# schematic-copy_2026-08-19.net
KiCad netlist of a schematic drawn in Altium Designer
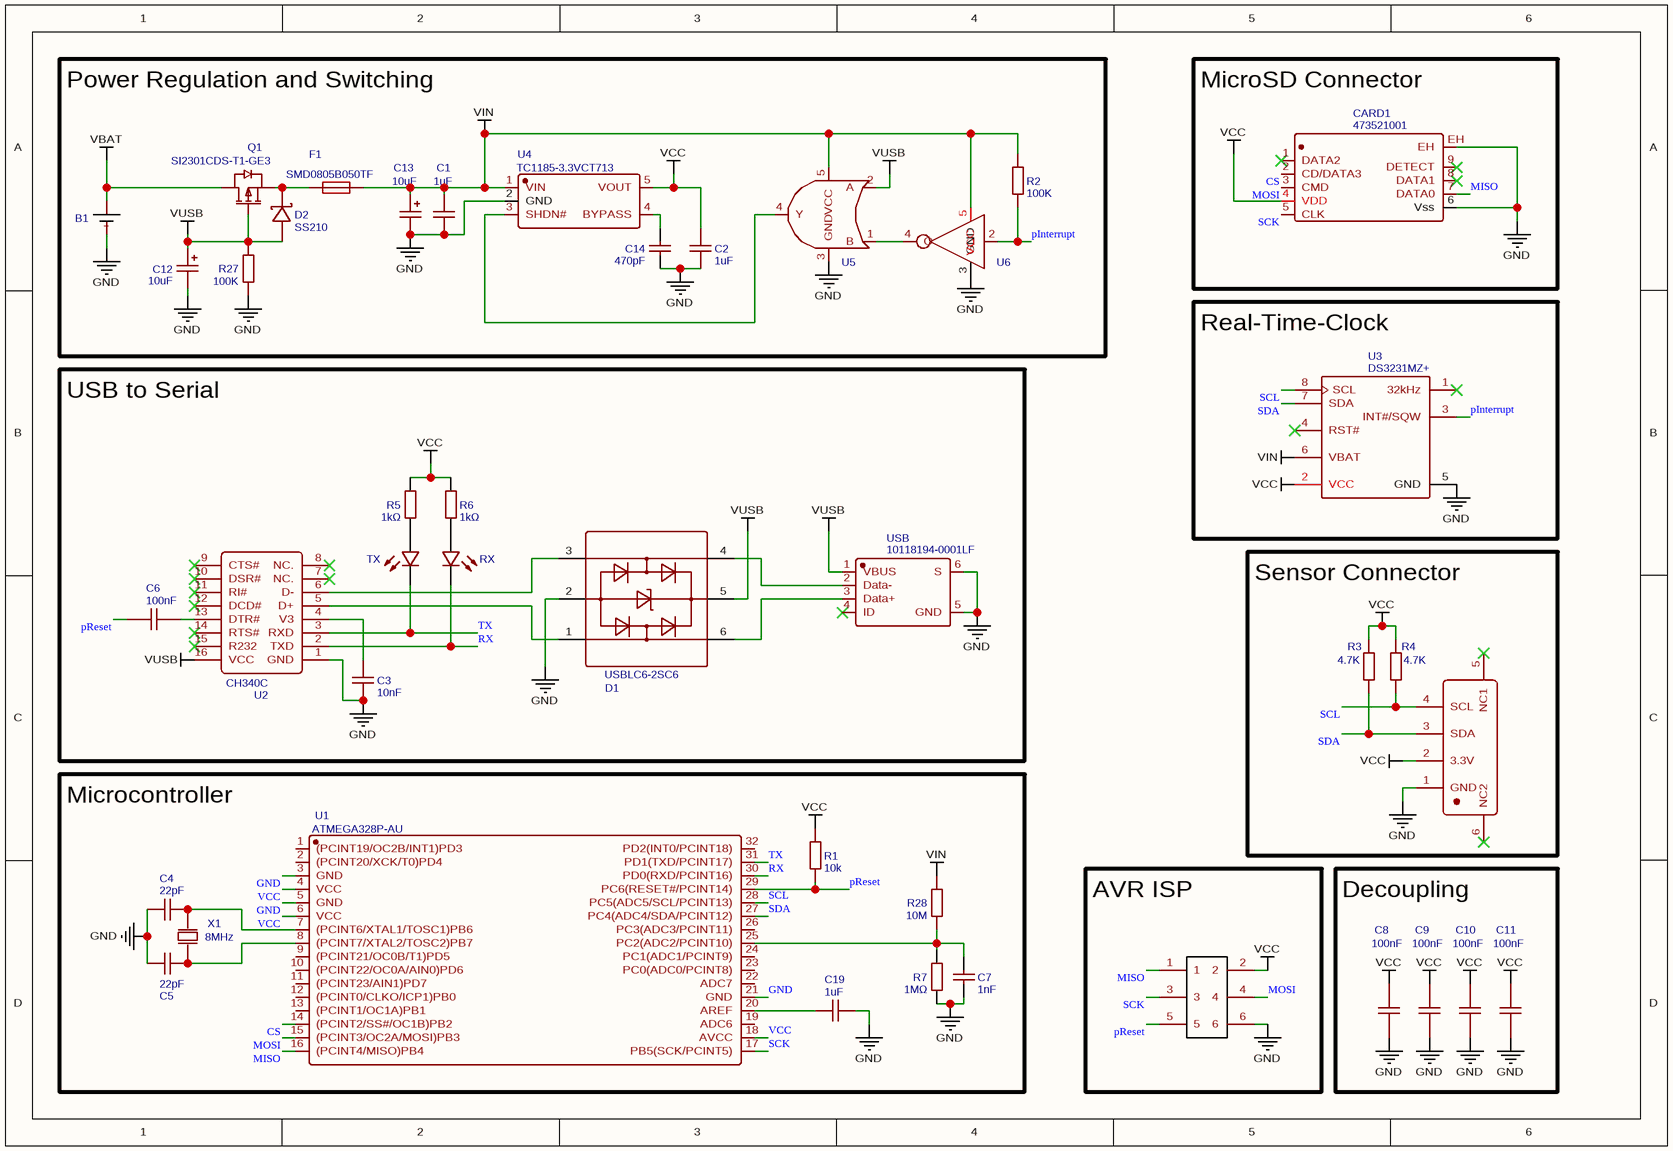
[diagram p0: schematic-copy_2026-08-19.schdoc]

(export (version "E")
  (design (tool "Eeschema 10.0.6"))
  (components
    (comp (ref "B1")
      (value "KEYSTONE 2460 1XAA")
      (fields
        (field (name "MANUFACTURER") "Keystone Electronics")
        (field (name "MANUFACTURER PART") "2460")
        (field (name "CONTRIBUTOR") "montezuma1970")
      )
      (libsource (lib "altium-import") (part "root_0_KEYSTONE 2460 1XAA_"))
    )
    (comp (ref "C1")
      (value "1uF")
      (fields (field (name "MANUFACTURER PART") "CL10A105KB8NNNC") (field (name "MANUFACTURER") "SAMSUNG"))
      (libsource (lib "altium-import") (part "root_1_1uF_"))
    )
    (comp (ref "C2")
      (value "1uF")
      (fields (field (name "MANUFACTURER PART") "CL10A105KB8NNNC") (field (name "MANUFACTURER") "SAMSUNG"))
      (libsource (lib "altium-import") (part "root_3_1uF_"))
    )
    (comp (ref "C3")
      (value "10nF")
      (fields (field (name "MANUFACTURER") "FH(风华)") (field (name "MANUFACTURER PART") "0603B103K500NT"))
      (libsource (lib "altium-import") (part "root_3_10nF_"))
    )
    (comp (ref "C4")
      (value "22pF")
      (fields (field (name "MANUFACTURER PART") "CL10C220JB8NNNC") (field (name "MANUFACTURER") "SAMSUNG"))
      (libsource (lib "altium-import") (part "root_2_22pF_"))
    )
    (comp (ref "C5")
      (value "22pF")
      (fields (field (name "MANUFACTURER PART") "CL10C220JB8NNNC") (field (name "MANUFACTURER") "SAMSUNG"))
      (libsource (lib "altium-import") (part "root_0_22pF_"))
    )
    (comp (ref "C6")
      (value "100nF")
      (fields (field (name "MANUFACTURER") "YAGEO") (field (name "MANUFACTURER PART") "CC0603KRX7R9BB104"))
      (libsource (lib "altium-import") (part "root_2_100nF_"))
    )
    (comp (ref "C7")
      (value "1nF")
      (fields
        (field (name "MANUFACTURER PART") "CL10B102KB8NNNC")
        (field (name "MANUFACTURER") "SAMSUNG(三星)")
      )
      (libsource (lib "altium-import") (part "root_1_1nF_"))
    )
    (comp (ref "C8")
      (value "100nF")
      (fields (field (name "MANUFACTURER") "YAGEO") (field (name "MANUFACTURER PART") "CC0603KRX7R9BB104"))
      (libsource (lib "altium-import") (part "root_1_100nF_"))
    )
    (comp (ref "C9")
      (value "100nF")
      (fields (field (name "MANUFACTURER") "YAGEO") (field (name "MANUFACTURER PART") "CC0603KRX7R9BB104"))
      (libsource (lib "altium-import") (part "root_1_100nF_"))
    )
    (comp (ref "C10")
      (value "100nF")
      (fields (field (name "MANUFACTURER") "YAGEO") (field (name "MANUFACTURER PART") "CC0603KRX7R9BB104"))
      (libsource (lib "altium-import") (part "root_1_100nF_"))
    )
    (comp (ref "C11")
      (value "100nF")
      (fields (field (name "MANUFACTURER") "YAGEO") (field (name "MANUFACTURER PART") "CC0603KRX7R9BB104"))
      (libsource (lib "altium-import") (part "root_1_100nF_"))
    )
    (comp (ref "C12")
      (value "10uF")
      (fields (field (name "MANUFACTURER") "AVX") (field (name "MANUFACTURER PART") "TAJA106K016RNJ"))
      (libsource (lib "altium-import") (part "root_1_10uF_"))
    )
    (comp (ref "C13")
      (value "10uF")
      (fields (field (name "MANUFACTURER") "AVX") (field (name "MANUFACTURER PART") "TAJA106K016RNJ"))
      (libsource (lib "altium-import") (part "root_1_10uF_"))
    )
    (comp (ref "C14")
      (value "470pF")
      (fields (field (name "MANUFACTURER") "FH(风华)") (field (name "MANUFACTURER PART") "0603B471K500NT"))
      (libsource (lib "altium-import") (part "root_1_470pF_"))
    )
    (comp (ref "C19")
      (value "1uF")
      (fields (field (name "MANUFACTURER PART") "CL10A105KB8NNNC") (field (name "MANUFACTURER") "SAMSUNG"))
      (libsource (lib "altium-import") (part "root_2_1uF_"))
    )
    (comp (ref "CARD1")
      (value "473521001")
      (fields (field (name "MANUFACTURER") "MOLEX") (field (name "CONTRIBUTOR") "LCSC"))
      (libsource (lib "altium-import") (part "root_0_473521001_"))
    )
    (comp (ref "D1")
      (value "USBLC6-2SC6")
      (fields (field (name "MANUFACTURER") "ST(意法半导体)"))
      (libsource (lib "altium-import") (part "root_0_USBLC6-2SC6_"))
    )
    (comp (ref "D2")
      (value "SS210")
      (fields (field (name "MANUFACTURER") "MDD"))
      (libsource (lib "altium-import") (part "root_3_SS210_"))
    )
    (comp (ref "F1")
      (value "SMD0805B050TF")
      (fields (field (name "MANUFACTURER") "Brightking(君耀电子)") (field (name "CONTRIBUTOR") "LCSC"))
      (libsource (lib "altium-import") (part "root_0_SMD0805B050TF_"))
    )
    (comp (ref "ICSP")
      (value "ICSP_2X3")
      (fields (field (name "CONTRIBUTOR") "hvergelmir.eed04"))
      (libsource (lib "altium-import") (part "root_0_ICSP_2X3_"))
    )
    (comp (ref "Q1")
      (value "SI2301CDS-T1-GE3")
      (fields (field (name "MANUFACTURER") "VISHAY"))
      (libsource (lib "altium-import") (part "root_3_SI2301CDS-T1-GE3_"))
    )
    (comp (ref "R1")
      (value "10k")
      (fields (field (name "MANUFACTURER") "UniOhm") (field (name "MANUFACTURER PART") "0603WAF1002T5E"))
      (libsource (lib "altium-import") (part "root_1_10k_"))
    )
    (comp (ref "R2")
      (value "100K")
      (fields (field (name "MANUFACTURER") "UniOhm") (field (name "MANUFACTURER PART") "0603WAF1003T5E"))
      (libsource (lib "altium-import") (part "root_1_100K_"))
    )
    (comp (ref "R3")
      (value "4.7K")
      (fields (field (name "MANUFACTURER") "UniOhm") (field (name "MANUFACTURER PART") "0603WAF4701T5E"))
      (libsource (lib "altium-import") (part "root_1_4.7K_"))
    )
    (comp (ref "R4")
      (value "4.7K")
      (fields (field (name "MANUFACTURER") "UniOhm") (field (name "MANUFACTURER PART") "0603WAF4701T5E"))
      (libsource (lib "altium-import") (part "root_1_4.7K_"))
    )
    (comp (ref "R5")
      (value "1kΩ")
      (fields
        (field (name "MANUFACTURER") "UNI-ROYAL(厚声)")
        (field (name "MANUFACTURER PART") "0603WAF1001T5E")
      )
      (libsource (lib "altium-import") (part "root_1_1kΩ_"))
    )
    (comp (ref "R6")
      (value "1kΩ")
      (fields
        (field (name "MANUFACTURER") "UNI-ROYAL(厚声)")
        (field (name "MANUFACTURER PART") "0603WAF1001T5E")
      )
      (libsource (lib "altium-import") (part "root_1_1kΩ_"))
    )
    (comp (ref "R7")
      (value "1MΩ")
      (fields
        (field (name "MANUFACTURER") "UNI-ROYAL(厚声)")
        (field (name "MANUFACTURER PART") "0603WAF1004T5E")
      )
      (libsource (lib "altium-import") (part "root_1_1MΩ_"))
    )
    (comp (ref "R27")
      (value "100K")
      (fields (field (name "MANUFACTURER") "UniOhm") (field (name "MANUFACTURER PART") "0603WAF1003T5E"))
      (libsource (lib "altium-import") (part "root_1_100K_"))
    )
    (comp (ref "R28")
      (value "10M")
      (fields (field (name "MANUFACTURER") "UniOhm") (field (name "MANUFACTURER PART") "0603WAF1005T5E"))
      (libsource (lib "altium-import") (part "root_1_10M_"))
    )
    (comp (ref "RX")
      (value "19-213/Y2C-CQ2R2L/3T(CY)")
      (fields (field (name "MANUFACTURER") "EVERLIGHT(亿光)"))
      (libsource (lib "altium-import") (part "root_3_19-213/Y2C-CQ2R2L/3T(CY)_"))
    )
    (comp (ref "TX")
      (value "19-213/Y2C-CQ2R2L/3T(CY)")
      (fields (field (name "MANUFACTURER") "EVERLIGHT(亿光)"))
      (libsource (lib "") (part "root_3_19-213/Y2C-CQ2R2L/3T(CY)__1"))
    )
    (comp (ref "U1")
      (value "ATMEGA328P-AU")
      (fields (field (name "MANUFACTURER") "MICROCHIP"))
      (libsource (lib "altium-import") (part "root_0_ATMEGA328P-AU_"))
    )
    (comp (ref "U2")
      (value "CH340C")
      (fields (field (name "MANUFACTURER") "WCH"))
      (libsource (lib "altium-import") (part "root_0_CH340C_"))
    )
    (comp (ref "U3")
      (value "DS3231MZ+")
      (fields (field (name "MANUFACTURER") "MAXIM(美信)") (field (name "MANUFACTURER PART") "DS3231MZ+TRL"))
      (libsource (lib "altium-import") (part "root_0_DS3231MZ+_"))
    )
    (comp (ref "U4")
      (value "TC1185-3.3VCT713")
      (fields (field (name "MANUFACTURER") "MICROCHIP(美国微芯)"))
      (libsource (lib "altium-import") (part "root_0_TC1185-3.3VCT713_"))
    )
    (comp (ref "U5")
      (value "74AHC1G32GW,125")
      (fields (field (name "MANUFACTURER") "Nexperia") (field (name "CONTRIBUTOR") "Ted Langhorst"))
      (libsource (lib "altium-import") (part "root_0_74AHC1G32GW,125_"))
    )
    (comp (ref "U6")
      (value "SN74LVC1G14DCKR")
      (fields (field (name "MANUFACTURER") "TI(德州仪器)"))
      (libsource (lib "altium-import") (part "root_2_SN74LVC1G14DCKR_"))
    )
    (comp (ref "U11")
      (value "QWIIC")
      (fields (field (name "MANUFACTURER") "JST Sales America") (field (name "CONTRIBUTOR") "donhagen"))
      (libsource (lib "altium-import") (part "root_1_QWIIC_"))
    )
    (comp (ref "USB")
      (value "10118194-0001LF")
      (fields (field (name "MANUFACTURER") "Amphenol ICC") (field (name "CONTRIBUTOR") "LCSC"))
      (libsource (lib "altium-import") (part "root_0_10118194-0001LF_"))
    )
    (comp (ref "X1")
      (value "8MHz")
      (fields (field (name "MANUFACTURER") "YXC") (field (name "MANUFACTURER PART") "X50328MSB2GI"))
      (libsource (lib "altium-import") (part "root_1_8MHz_"))
    )
  )
  (nets
    (net (code "1") (name "/CS") (class "Default")
      (node (ref "CARD1") (pin "2") (pinfunction "CD/DATA3_2") (pintype "passive"))
      (node (ref "U1") (pin "14") (pinfunction "(PCINT2/SS#/OC1B)PB2_14") (pintype "passive"))
    )
    (net (code "2") (name "/MISO") (class "Default")
      (node (ref "CARD1") (pin "7") (pinfunction "DATA0_7") (pintype "passive"))
      (node (ref "ICSP") (pin "1") (pinfunction "1_1") (pintype "passive"))
      (node (ref "U1") (pin "16") (pinfunction "(PCINT4/MISO)PB4_16") (pintype "passive"))
    )
    (net (code "3") (name "/MOSI") (class "Default")
      (node (ref "CARD1") (pin "3") (pinfunction "CMD_3") (pintype "passive"))
      (node (ref "ICSP") (pin "4") (pinfunction "4_4") (pintype "passive"))
      (node (ref "U1") (pin "15") (pinfunction "(PCINT3/OC2A/MOSI)PB3_15") (pintype "passive"))
    )
    (net (code "4") (name "/RX") (class "Default")
      (node (ref "RX") (pin "2") (pinfunction "C_2") (pintype "passive"))
      (node (ref "U1") (pin "30") (pinfunction "PD0(RXD/PCINT16)_30") (pintype "passive"))
      (node (ref "U2") (pin "2") (pinfunction "TXD_2") (pintype "passive"))
    )
    (net (code "5") (name "/SCK") (class "Default")
      (node (ref "CARD1") (pin "5") (pinfunction "CLK_5") (pintype "passive"))
      (node (ref "ICSP") (pin "3") (pinfunction "3_3") (pintype "passive"))
      (node (ref "U1") (pin "17") (pinfunction "PB5(SCK/PCINT5)_17") (pintype "passive"))
    )
    (net (code "6") (name "/SCL") (class "Default")
      (node (ref "R4") (pin "1") (pinfunction "1_1") (pintype "passive"))
      (node (ref "U1") (pin "28") (pinfunction "PC5(ADC5/SCL/PCINT13)_28") (pintype "passive"))
      (node (ref "U11") (pin "4") (pinfunction "SCL_4") (pintype "passive"))
      (node (ref "U3") (pin "8") (pinfunction "SCL_8") (pintype "passive"))
    )
    (net (code "7") (name "/SDA") (class "Default")
      (node (ref "R3") (pin "1") (pinfunction "1_1") (pintype "passive"))
      (node (ref "U1") (pin "27") (pinfunction "PC4(ADC4/SDA/PCINT12)_27") (pintype "passive"))
      (node (ref "U11") (pin "3") (pinfunction "SDA_3") (pintype "passive"))
      (node (ref "U3") (pin "7") (pinfunction "SDA_7") (pintype "passive"))
    )
    (net (code "8") (name "/TX") (class "Default")
      (node (ref "TX") (pin "2") (pinfunction "C_2") (pintype "passive"))
      (node (ref "U1") (pin "31") (pinfunction "PD1(TXD/PCINT17)_31") (pintype "passive"))
      (node (ref "U2") (pin "3") (pinfunction "RXD_3") (pintype "passive"))
    )
    (net (code "9") (name "/pInterrupt") (class "Default")
      (node (ref "R2") (pin "1") (pinfunction "1_1") (pintype "passive"))
      (node (ref "U3") (pin "3") (pinfunction "INT#/SQW_3") (pintype "passive"))
      (node (ref "U6") (pin "2") (pinfunction "I_2") (pintype "passive"))
    )
    (net (code "10") (name "/pReset") (class "Default")
      (node (ref "C6") (pin "2") (pinfunction "2_2") (pintype "passive"))
      (node (ref "ICSP") (pin "5") (pinfunction "5_5") (pintype "passive"))
      (node (ref "R1") (pin "1") (pinfunction "1_1") (pintype "passive"))
      (node (ref "U1") (pin "29") (pinfunction "PC6(RESET#/PCINT14)_29") (pintype "passive"))
    )
    (net (code "11") (name "GND") (class "Default")
      (node (ref "B1") (pin "2") (pinfunction "-_2") (pintype "passive"))
      (node (ref "C1") (pin "1") (pinfunction "1_1") (pintype "passive"))
      (node (ref "C10") (pin "1") (pinfunction "1_1") (pintype "passive"))
      (node (ref "C11") (pin "1") (pinfunction "1_1") (pintype "passive"))
      (node (ref "C12") (pin "2") (pinfunction "2_2") (pintype "passive"))
      (node (ref "C13") (pin "2") (pinfunction "2_2") (pintype "passive"))
      (node (ref "C14") (pin "1") (pinfunction "1_1") (pintype "passive"))
      (node (ref "C19") (pin "1") (pinfunction "1_1") (pintype "passive"))
      (node (ref "C2") (pin "2") (pinfunction "2_2") (pintype "passive"))
      (node (ref "C3") (pin "2") (pinfunction "2_2") (pintype "passive"))
      (node (ref "C4") (pin "2") (pinfunction "2_2") (pintype "passive"))
      (node (ref "C5") (pin "1") (pinfunction "1_1") (pintype "passive"))
      (node (ref "C7") (pin "1") (pinfunction "1_1") (pintype "passive"))
      (node (ref "C8") (pin "1") (pinfunction "1_1") (pintype "passive"))
      (node (ref "C9") (pin "1") (pinfunction "1_1") (pintype "passive"))
      (node (ref "CARD1") (pin "6") (pinfunction "Vss_6") (pintype "passive"))
      (node (ref "CARD1") (pin "EH") (pinfunction "EH_EH") (pintype "passive"))
      (node (ref "D1") (pin "2") (pinfunction "2_2") (pintype "passive"))
      (node (ref "ICSP") (pin "6") (pinfunction "6_6") (pintype "passive"))
      (node (ref "R27") (pin "1") (pinfunction "1_1") (pintype "passive"))
      (node (ref "R7") (pin "1") (pinfunction "1_1") (pintype "passive"))
      (node (ref "U1") (pin "21") (pinfunction "GND_21") (pintype "passive"))
      (node (ref "U1") (pin "3") (pinfunction "GND_3") (pintype "passive"))
      (node (ref "U1") (pin "5") (pinfunction "GND_5") (pintype "passive"))
      (node (ref "U11") (pin "1") (pinfunction "GND_1") (pintype "passive"))
      (node (ref "U2") (pin "1") (pinfunction "GND_1") (pintype "passive"))
      (node (ref "U3") (pin "5") (pinfunction "GND_5") (pintype "passive"))
      (node (ref "U4") (pin "2") (pinfunction "GND_2") (pintype "passive"))
      (node (ref "U5") (pin "3") (pinfunction "GND_3") (pintype "passive"))
      (node (ref "U6") (pin "3") (pinfunction "GND_3") (pintype "passive"))
      (node (ref "USB") (pin "5") (pinfunction "GND_5") (pintype "passive"))
      (node (ref "USB") (pin "6") (pinfunction "S_6") (pintype "passive"))
    )
    (net (code "12") (name "Net-(D2-K)") (class "Default")
      (node (ref "D2") (pin "1") (pinfunction "K_1") (pintype "passive"))
      (node (ref "F1") (pin "1") (pinfunction "1_1") (pintype "passive"))
      (node (ref "Q1") (pin "2") (pinfunction "S_2") (pintype "passive"))
    )
    (net (code "13") (name "Net-(RX-A)") (class "Default")
      (node (ref "R6") (pin "1") (pinfunction "1_1") (pintype "passive"))
      (node (ref "RX") (pin "1") (pinfunction "A_1") (pintype "passive"))
    )
    (net (code "14") (name "Net-(TX-A)") (class "Default")
      (node (ref "R5") (pin "1") (pinfunction "1_1") (pintype "passive"))
      (node (ref "TX") (pin "1") (pinfunction "A_1") (pintype "passive"))
    )
    (net (code "15") (name "Net-(U1-(PCINT6{slash}XTAL1{slash}TOSC1)PB6)") (class "Default")
      (node (ref "C4") (pin "1") (pinfunction "1_1") (pintype "passive"))
      (node (ref "U1") (pin "7") (pinfunction "(PCINT6/XTAL1/TOSC1)PB6_7") (pintype "passive"))
      (node (ref "X1") (pin "2") (pinfunction "OSC2_2") (pintype "passive"))
    )
    (net (code "16") (name "Net-(U1-(PCINT7{slash}XTAL2{slash}TOSC2)PB7)") (class "Default")
      (node (ref "C5") (pin "2") (pinfunction "2_2") (pintype "passive"))
      (node (ref "U1") (pin "8") (pinfunction "(PCINT7/XTAL2/TOSC2)PB7_8") (pintype "passive"))
      (node (ref "X1") (pin "1") (pinfunction "OSC1_1") (pintype "passive"))
    )
    (net (code "17") (name "Net-(U1-AREF)") (class "Default")
      (node (ref "C19") (pin "2") (pinfunction "2_2") (pintype "passive"))
      (node (ref "U1") (pin "20") (pinfunction "AREF_20") (pintype "passive"))
    )
    (net (code "18") (name "Net-(U1-PC2(ADC2{slash}PCINT10))") (class "Default")
      (node (ref "C7") (pin "2") (pinfunction "2_2") (pintype "passive"))
      (node (ref "R28") (pin "1") (pinfunction "1_1") (pintype "passive"))
      (node (ref "R7") (pin "2") (pinfunction "2_2") (pintype "passive"))
      (node (ref "U1") (pin "25") (pinfunction "PC2(ADC2/PCINT10)_25") (pintype "passive"))
    )
    (net (code "19") (name "Net-(U2-D+)") (class "Default")
      (node (ref "D1") (pin "1") (pinfunction "1_1") (pintype "passive"))
      (node (ref "U2") (pin "5") (pinfunction "D+_5") (pintype "passive"))
    )
    (net (code "20") (name "Net-(U2-D-)") (class "Default")
      (node (ref "D1") (pin "3") (pinfunction "3_3") (pintype "passive"))
      (node (ref "U2") (pin "6") (pinfunction "D-_6") (pintype "passive"))
    )
    (net (code "21") (name "Net-(U2-DTR#)") (class "Default")
      (node (ref "C6") (pin "1") (pinfunction "1_1") (pintype "passive"))
      (node (ref "U2") (pin "13") (pinfunction "DTR#_13") (pintype "passive"))
    )
    (net (code "22") (name "Net-(U2-V3)") (class "Default")
      (node (ref "C3") (pin "1") (pinfunction "1_1") (pintype "passive"))
      (node (ref "U2") (pin "4") (pinfunction "V3_4") (pintype "passive"))
    )
    (net (code "23") (name "Net-(U4-BYPASS)") (class "Default")
      (node (ref "C14") (pin "2") (pinfunction "2_2") (pintype "passive"))
      (node (ref "U4") (pin "4") (pinfunction "BYPASS_4") (pintype "passive"))
    )
    (net (code "24") (name "Net-(U4-SHDN#)") (class "Default")
      (node (ref "U4") (pin "3") (pinfunction "SHDN#_3") (pintype "passive"))
      (node (ref "U5") (pin "4") (pinfunction "Y_4") (pintype "passive"))
    )
    (net (code "25") (name "Net-(U5-B)") (class "Default")
      (node (ref "U5") (pin "1") (pinfunction "B_1") (pintype "passive"))
      (node (ref "U6") (pin "4") (pinfunction "O_4") (pintype "passive"))
    )
    (net (code "26") (name "Net-(USB-Data+)") (class "Default")
      (node (ref "D1") (pin "6") (pinfunction "6_6") (pintype "passive"))
      (node (ref "USB") (pin "3") (pinfunction "Data+_3") (pintype "passive"))
    )
    (net (code "27") (name "Net-(USB-Data-)") (class "Default")
      (node (ref "D1") (pin "4") (pinfunction "4_4") (pintype "passive"))
      (node (ref "USB") (pin "2") (pinfunction "Data-_2") (pintype "passive"))
    )
    (net (code "28") (name "VBAT") (class "Default")
      (node (ref "B1") (pin "1") (pinfunction "+_1") (pintype "passive"))
      (node (ref "Q1") (pin "3") (pinfunction "D_3") (pintype "passive"))
    )
    (net (code "29") (name "VCC") (class "Default")
      (node (ref "C10") (pin "2") (pinfunction "2_2") (pintype "passive"))
      (node (ref "C11") (pin "2") (pinfunction "2_2") (pintype "passive"))
      (node (ref "C2") (pin "1") (pinfunction "1_1") (pintype "passive"))
      (node (ref "C8") (pin "2") (pinfunction "2_2") (pintype "passive"))
      (node (ref "C9") (pin "2") (pinfunction "2_2") (pintype "passive"))
      (node (ref "CARD1") (pin "4") (pinfunction "VDD_4") (pintype "passive"))
      (node (ref "ICSP") (pin "2") (pinfunction "2_2") (pintype "passive"))
      (node (ref "R1") (pin "2") (pinfunction "2_2") (pintype "passive"))
      (node (ref "R3") (pin "2") (pinfunction "2_2") (pintype "passive"))
      (node (ref "R4") (pin "2") (pinfunction "2_2") (pintype "passive"))
      (node (ref "R5") (pin "2") (pinfunction "2_2") (pintype "passive"))
      (node (ref "R6") (pin "2") (pinfunction "2_2") (pintype "passive"))
      (node (ref "U1") (pin "18") (pinfunction "AVCC_18") (pintype "passive"))
      (node (ref "U1") (pin "4") (pinfunction "VCC_4") (pintype "passive"))
      (node (ref "U1") (pin "6") (pinfunction "VCC_6") (pintype "passive"))
      (node (ref "U11") (pin "2") (pinfunction "3.3V_2") (pintype "passive"))
      (node (ref "U3") (pin "2") (pinfunction "VCC_2") (pintype "passive"))
      (node (ref "U4") (pin "5") (pinfunction "VOUT_5") (pintype "passive"))
    )
    (net (code "30") (name "VIN") (class "Default")
      (node (ref "C1") (pin "2") (pinfunction "2_2") (pintype "passive"))
      (node (ref "C13") (pin "1") (pinfunction "1_1") (pintype "passive"))
      (node (ref "F1") (pin "2") (pinfunction "2_2") (pintype "passive"))
      (node (ref "R2") (pin "2") (pinfunction "2_2") (pintype "passive"))
      (node (ref "R28") (pin "2") (pinfunction "2_2") (pintype "passive"))
      (node (ref "U3") (pin "6") (pinfunction "VBAT_6") (pintype "passive"))
      (node (ref "U4") (pin "1") (pinfunction "VIN_1") (pintype "passive"))
      (node (ref "U5") (pin "5") (pinfunction "VCC_5") (pintype "passive"))
      (node (ref "U6") (pin "5") (pinfunction "VCC_5") (pintype "passive"))
    )
    (net (code "31") (name "VUSB") (class "Default")
      (node (ref "C12") (pin "1") (pinfunction "1_1") (pintype "passive"))
      (node (ref "D1") (pin "5") (pinfunction "5_5") (pintype "passive"))
      (node (ref "D2") (pin "2") (pinfunction "A_2") (pintype "passive"))
      (node (ref "Q1") (pin "1") (pinfunction "G_1") (pintype "passive"))
      (node (ref "R27") (pin "2") (pinfunction "2_2") (pintype "passive"))
      (node (ref "U2") (pin "16") (pinfunction "VCC_16") (pintype "passive"))
      (node (ref "U5") (pin "2") (pinfunction "A_2") (pintype "passive"))
      (node (ref "USB") (pin "1") (pinfunction "VBUS_1") (pintype "passive"))
    )
    (net (code "32") (name "unconnected-(CARD1-DATA1-Pad8)") (class "Default")
      (node (ref "CARD1") (pin "8") (pinfunction "DATA1_8") (pintype "passive+no_connect"))
    )
    (net (code "33") (name "unconnected-(CARD1-DATA2-Pad1)") (class "Default")
      (node (ref "CARD1") (pin "1") (pinfunction "DATA2_1") (pintype "passive+no_connect"))
    )
    (net (code "34") (name "unconnected-(CARD1-DETECT-Pad9)") (class "Default")
      (node (ref "CARD1") (pin "9") (pinfunction "DETECT_9") (pintype "passive+no_connect"))
    )
    (net (code "35") (name "unconnected-(U1-(PCINT0{slash}CLKO{slash}ICP1)PB0-Pad12)") (class "Default")
      (node (ref "U1") (pin "12") (pinfunction "(PCINT0/CLKO/ICP1)PB0_12") (pintype "passive"))
    )
    (net (code "36") (name "unconnected-(U1-(PCINT1{slash}OC1A)PB1-Pad13)") (class "Default")
      (node (ref "U1") (pin "13") (pinfunction "(PCINT1/OC1A)PB1_13") (pintype "passive"))
    )
    (net (code "37") (name "unconnected-(U1-(PCINT19{slash}OC2B{slash}INT1)PD3-Pad1)") (class "Default")
      (node (ref "U1") (pin "1") (pinfunction "(PCINT19/OC2B/INT1)PD3_1") (pintype "passive"))
    )
    (net (code "38") (name "unconnected-(U1-(PCINT20{slash}XCK{slash}T0)PD4-Pad2)") (class "Default")
      (node (ref "U1") (pin "2") (pinfunction "(PCINT20/XCK/T0)PD4_2") (pintype "passive"))
    )
    (net (code "39") (name "unconnected-(U1-(PCINT21{slash}OC0B{slash}T1)PD5-Pad9)") (class "Default")
      (node (ref "U1") (pin "9") (pinfunction "(PCINT21/OC0B/T1)PD5_9") (pintype "passive"))
    )
    (net (code "40") (name "unconnected-(U1-(PCINT22{slash}OC0A{slash}AIN0)PD6-Pad10)") (class "Default")
      (node (ref "U1") (pin "10") (pinfunction "(PCINT22/OC0A/AIN0)PD6_10") (pintype "passive"))
    )
    (net (code "41") (name "unconnected-(U1-(PCINT23{slash}AIN1)PD7-Pad11)") (class "Default")
      (node (ref "U1") (pin "11") (pinfunction "(PCINT23/AIN1)PD7_11") (pintype "passive"))
    )
    (net (code "42") (name "unconnected-(U1-ADC6-Pad19)") (class "Default")
      (node (ref "U1") (pin "19") (pinfunction "ADC6_19") (pintype "passive"))
    )
    (net (code "43") (name "unconnected-(U1-ADC7-Pad22)") (class "Default")
      (node (ref "U1") (pin "22") (pinfunction "ADC7_22") (pintype "passive"))
    )
    (net (code "44") (name "unconnected-(U1-PC0(ADC0{slash}PCINT8)-Pad23)") (class "Default")
      (node (ref "U1") (pin "23") (pinfunction "PC0(ADC0/PCINT8)_23") (pintype "passive"))
    )
    (net (code "45") (name "unconnected-(U1-PC1(ADC1{slash}PCINT9)-Pad24)") (class "Default")
      (node (ref "U1") (pin "24") (pinfunction "PC1(ADC1/PCINT9)_24") (pintype "passive"))
    )
    (net (code "46") (name "unconnected-(U1-PC3(ADC3{slash}PCINT11)-Pad26)") (class "Default")
      (node (ref "U1") (pin "26") (pinfunction "PC3(ADC3/PCINT11)_26") (pintype "passive"))
    )
    (net (code "47") (name "unconnected-(U1-PD2(INT0{slash}PCINT18)-Pad32)") (class "Default")
      (node (ref "U1") (pin "32") (pinfunction "PD2(INT0/PCINT18)_32") (pintype "passive"))
    )
    (net (code "48") (name "unconnected-(U2-CTS#-Pad9)") (class "Default")
      (node (ref "U2") (pin "9") (pinfunction "CTS#_9") (pintype "passive+no_connect"))
    )
    (net (code "49") (name "unconnected-(U2-DCD#-Pad12)") (class "Default")
      (node (ref "U2") (pin "12") (pinfunction "DCD#_12") (pintype "passive+no_connect"))
    )
    (net (code "50") (name "unconnected-(U2-DSR#-Pad10)") (class "Default")
      (node (ref "U2") (pin "10") (pinfunction "DSR#_10") (pintype "passive+no_connect"))
    )
    (net (code "51") (name "unconnected-(U2-NC.-Pad7)") (class "Default")
      (node (ref "U2") (pin "7") (pinfunction "NC._7") (pintype "passive+no_connect"))
    )
    (net (code "52") (name "unconnected-(U2-NC.-Pad8)") (class "Default")
      (node (ref "U2") (pin "8") (pinfunction "NC._8") (pintype "passive+no_connect"))
    )
    (net (code "53") (name "unconnected-(U2-R232-Pad15)") (class "Default")
      (node (ref "U2") (pin "15") (pinfunction "R232_15") (pintype "passive+no_connect"))
    )
    (net (code "54") (name "unconnected-(U2-RI#-Pad11)") (class "Default")
      (node (ref "U2") (pin "11") (pinfunction "RI#_11") (pintype "passive+no_connect"))
    )
    (net (code "55") (name "unconnected-(U2-RTS#-Pad14)") (class "Default")
      (node (ref "U2") (pin "14") (pinfunction "RTS#_14") (pintype "passive+no_connect"))
    )
    (net (code "56") (name "unconnected-(U3-32kHz-Pad1)") (class "Default")
      (node (ref "U3") (pin "1") (pinfunction "32kHz_1") (pintype "passive+no_connect"))
    )
    (net (code "57") (name "unconnected-(U3-RST#-Pad4)") (class "Default")
      (node (ref "U3") (pin "4") (pinfunction "RST#_4") (pintype "passive+no_connect"))
    )
    (net (code "58") (name "unconnected-(U11-NC1-Pad5)") (class "Default")
      (node (ref "U11") (pin "5") (pinfunction "NC1_5") (pintype "passive+no_connect"))
    )
    (net (code "59") (name "unconnected-(U11-NC2-Pad6)") (class "Default")
      (node (ref "U11") (pin "6") (pinfunction "NC2_6") (pintype "passive+no_connect"))
    )
    (net (code "60") (name "unconnected-(USB-ID-Pad4)") (class "Default")
      (node (ref "USB") (pin "4") (pinfunction "ID_4") (pintype "passive+no_connect"))
    )
  )
)
